# arpie_cv_tab.net
KiCad netlist of a schematic drawn in EAGLE
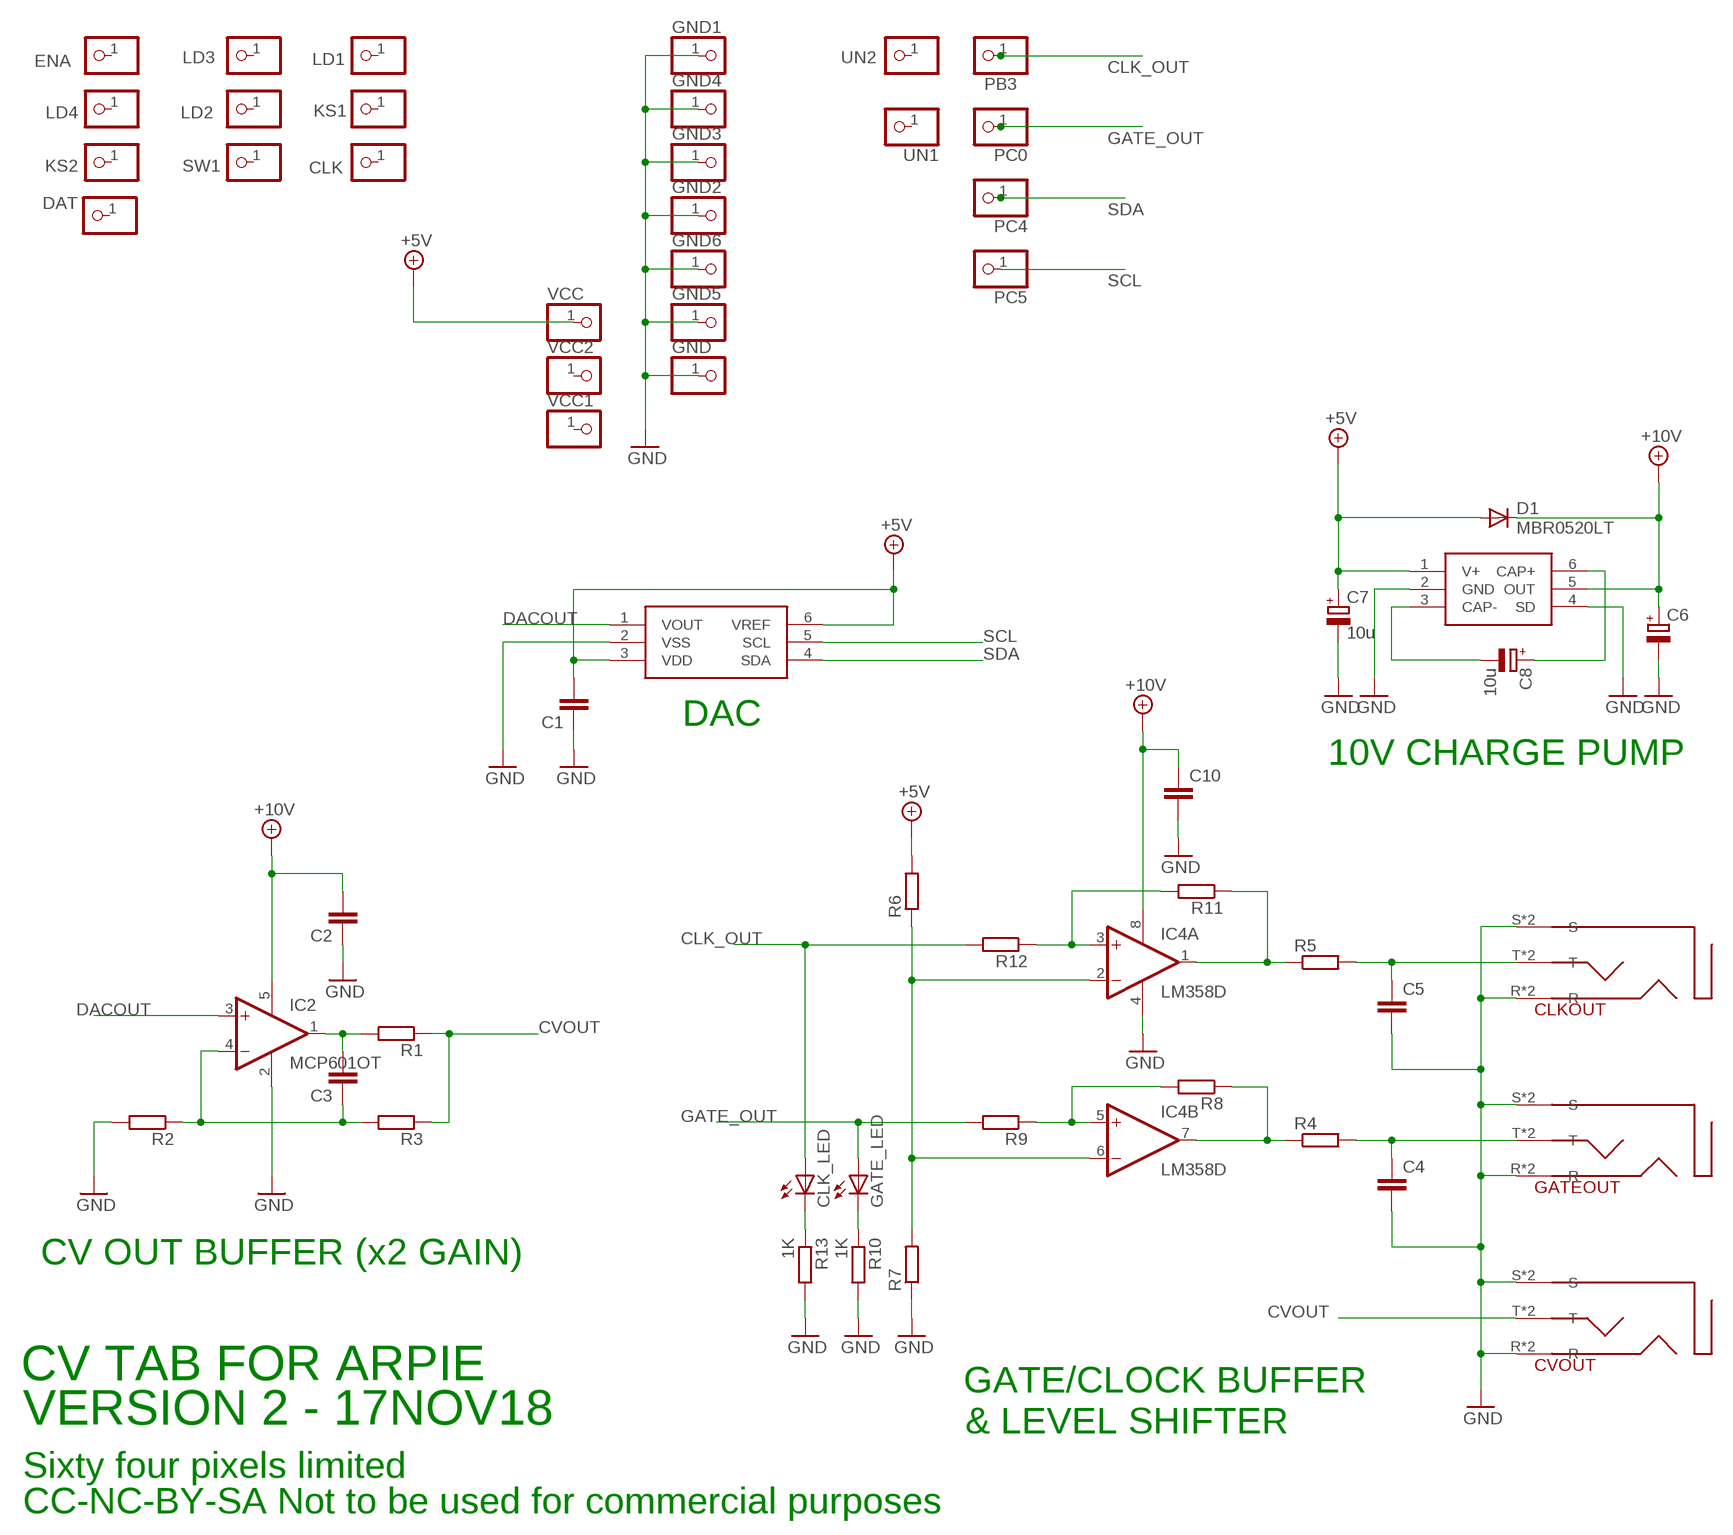
[diagram p0: schematic, sheet 1]

(export (version "E")
  (design (tool "Eeschema 10.0.6"))
  (components
    (comp (ref "C1")
      (value "C-EUC0805")
      (footprint "eagle-import:C0805")
      (libsource (lib "eagle-import") (part "C-EUC0805"))
    )
    (comp (ref "C2")
      (value "C-EUC0805")
      (footprint "eagle-import:C0805")
      (libsource (lib "eagle-import") (part "C-EUC0805"))
    )
    (comp (ref "C3")
      (value "C-EUC0805")
      (footprint "eagle-import:C0805")
      (libsource (lib "eagle-import") (part "C-EUC0805"))
    )
    (comp (ref "C4")
      (value "C-EUC0805")
      (footprint "eagle-import:C0805")
      (libsource (lib "eagle-import") (part "C-EUC0805"))
    )
    (comp (ref "C5")
      (value "C-EUC0805")
      (footprint "eagle-import:C0805")
      (libsource (lib "eagle-import") (part "C-EUC0805"))
    )
    (comp (ref "C6")
      (value "CPOL-EUSMCA")
      (footprint "eagle-import:SMC_A")
      (libsource (lib "eagle-import") (part "CPOL-EUSMCA"))
    )
    (comp (ref "C7")
      (value "10u")
      (footprint "eagle-import:SMC_A")
      (libsource (lib "eagle-import") (part "CPOL-EUSMCA"))
    )
    (comp (ref "C8")
      (value "10u")
      (footprint "eagle-import:SMC_A")
      (libsource (lib "eagle-import") (part "CPOL-EUSMCA"))
    )
    (comp (ref "C10")
      (value "C-EUC0805")
      (footprint "eagle-import:C0805")
      (libsource (lib "eagle-import") (part "C-EUC0805"))
    )
    (comp (ref "CLK")
      (value "PINHD-1X1")
      (footprint "eagle-import:1X01")
      (libsource (lib "eagle-import") (part "PINHD-1X1"))
    )
    (comp (ref "CLKOUT")
      (value "SMD35MMJACK")
      (footprint "eagle-import:SMD35MMJACK")
      (libsource (lib "eagle-import") (part "SMD35MMJACK"))
    )
    (comp (ref "CLK_LED")
      (value "LED3MM")
      (footprint "eagle-import:LED3MM")
      (libsource (lib "eagle-import") (part "LED3MM"))
    )
    (comp (ref "CVOUT")
      (value "SMD35MMJACK")
      (footprint "eagle-import:SMD35MMJACK")
      (libsource (lib "eagle-import") (part "SMD35MMJACK"))
    )
    (comp (ref "D1")
      (value "MBR0520LT")
      (footprint "eagle-import:SOD123")
      (libsource (lib "eagle-import") (part "MBR0520LT"))
    )
    (comp (ref "DAT")
      (value "PINHD-1X1")
      (footprint "eagle-import:1X01")
      (libsource (lib "eagle-import") (part "PINHD-1X1"))
    )
    (comp (ref "ENA")
      (value "PINHD-1X1")
      (footprint "eagle-import:1X01")
      (libsource (lib "eagle-import") (part "PINHD-1X1"))
    )
    (comp (ref "GATEOUT")
      (value "SMD35MMJACK")
      (footprint "eagle-import:SMD35MMJACK")
      (libsource (lib "eagle-import") (part "SMD35MMJACK"))
    )
    (comp (ref "GATE_LED")
      (value "LED3MM")
      (footprint "eagle-import:LED3MM")
      (libsource (lib "eagle-import") (part "LED3MM"))
    )
    (comp (ref "GND")
      (value "PINHD-1X1")
      (footprint "eagle-import:1X01")
      (libsource (lib "eagle-import") (part "PINHD-1X1"))
    )
    (comp (ref "GND1")
      (value "PINHD-1X1")
      (footprint "eagle-import:1X01")
      (libsource (lib "eagle-import") (part "PINHD-1X1"))
    )
    (comp (ref "GND2")
      (value "PINHD-1X1")
      (footprint "eagle-import:1X01")
      (libsource (lib "eagle-import") (part "PINHD-1X1"))
    )
    (comp (ref "GND3")
      (value "PINHD-1X1")
      (footprint "eagle-import:1X01")
      (libsource (lib "eagle-import") (part "PINHD-1X1"))
    )
    (comp (ref "GND4")
      (value "PINHD-1X1")
      (footprint "eagle-import:1X01")
      (libsource (lib "eagle-import") (part "PINHD-1X1"))
    )
    (comp (ref "GND5")
      (value "PINHD-1X1")
      (footprint "eagle-import:1X01")
      (libsource (lib "eagle-import") (part "PINHD-1X1"))
    )
    (comp (ref "GND6")
      (value "PINHD-1X1")
      (footprint "eagle-import:1X01")
      (libsource (lib "eagle-import") (part "PINHD-1X1"))
    )
    (comp (ref "IC1")
      (value "MCP4726")
      (footprint "eagle-import:SOT23-6")
      (libsource (lib "eagle-import") (part "MCP4726"))
    )
    (comp (ref "IC2")
      (value "MCP601OT")
      (footprint "eagle-import:SOT23-5")
      (libsource (lib "eagle-import") (part "MCP601OT"))
    )
    (comp (ref "IC3")
      (value "LM27675M5_CHARGEPUMP")
      (footprint "eagle-import:SOT23-6")
      (libsource (lib "eagle-import") (part "LM27675M5_CHARGEPUMP"))
    )
    (comp (ref "IC4")
      (value "LM358D")
      (footprint "eagle-import:SO08")
      (libsource (lib "eagle-import") (part "LM358D"))
    )
    (comp (ref "KS1")
      (value "PINHD-1X1")
      (footprint "eagle-import:1X01")
      (libsource (lib "eagle-import") (part "PINHD-1X1"))
    )
    (comp (ref "KS2")
      (value "PINHD-1X1")
      (footprint "eagle-import:1X01")
      (libsource (lib "eagle-import") (part "PINHD-1X1"))
    )
    (comp (ref "LD1")
      (value "PINHD-1X1")
      (footprint "eagle-import:1X01")
      (libsource (lib "eagle-import") (part "PINHD-1X1"))
    )
    (comp (ref "LD2")
      (value "PINHD-1X1")
      (footprint "eagle-import:1X01")
      (libsource (lib "eagle-import") (part "PINHD-1X1"))
    )
    (comp (ref "LD3")
      (value "PINHD-1X1")
      (footprint "eagle-import:1X01")
      (libsource (lib "eagle-import") (part "PINHD-1X1"))
    )
    (comp (ref "LD4")
      (value "PINHD-1X1")
      (footprint "eagle-import:1X01")
      (libsource (lib "eagle-import") (part "PINHD-1X1"))
    )
    (comp (ref "PB3")
      (value "PINHD-1X1")
      (footprint "eagle-import:1X01")
      (libsource (lib "eagle-import") (part "PINHD-1X1"))
    )
    (comp (ref "PC0")
      (value "PINHD-1X1")
      (footprint "eagle-import:1X01")
      (libsource (lib "eagle-import") (part "PINHD-1X1"))
    )
    (comp (ref "PC4")
      (value "PINHD-1X1")
      (footprint "eagle-import:1X01")
      (libsource (lib "eagle-import") (part "PINHD-1X1"))
    )
    (comp (ref "PC5")
      (value "PINHD-1X1")
      (footprint "eagle-import:1X01")
      (libsource (lib "eagle-import") (part "PINHD-1X1"))
    )
    (comp (ref "R1")
      (value "R-EU_R0805")
      (footprint "eagle-import:R0805")
      (libsource (lib "eagle-import") (part "R-EU_R0805"))
    )
    (comp (ref "R2")
      (value "R-EU_R0805")
      (footprint "eagle-import:R0805")
      (libsource (lib "eagle-import") (part "R-EU_R0805"))
    )
    (comp (ref "R3")
      (value "R-EU_R0805")
      (footprint "eagle-import:R0805")
      (libsource (lib "eagle-import") (part "R-EU_R0805"))
    )
    (comp (ref "R4")
      (value "R-EU_R0805")
      (footprint "eagle-import:R0805")
      (libsource (lib "eagle-import") (part "R-EU_R0805"))
    )
    (comp (ref "R5")
      (value "R-EU_R0805")
      (footprint "eagle-import:R0805")
      (libsource (lib "eagle-import") (part "R-EU_R0805"))
    )
    (comp (ref "R6")
      (value "R-EU_R0805")
      (footprint "eagle-import:R0805")
      (libsource (lib "eagle-import") (part "R-EU_R0805"))
    )
    (comp (ref "R7")
      (value "R-EU_R0805")
      (footprint "eagle-import:R0805")
      (libsource (lib "eagle-import") (part "R-EU_R0805"))
    )
    (comp (ref "R8")
      (value "R-EU_R0805")
      (footprint "eagle-import:R0805")
      (libsource (lib "eagle-import") (part "R-EU_R0805"))
    )
    (comp (ref "R9")
      (value "R-EU_R0805")
      (footprint "eagle-import:R0805")
      (libsource (lib "eagle-import") (part "R-EU_R0805"))
    )
    (comp (ref "R10")
      (value "1K")
      (footprint "eagle-import:R0805")
      (libsource (lib "eagle-import") (part "R-EU_R0805"))
    )
    (comp (ref "R11")
      (value "R-EU_R0805")
      (footprint "eagle-import:R0805")
      (libsource (lib "eagle-import") (part "R-EU_R0805"))
    )
    (comp (ref "R12")
      (value "R-EU_R0805")
      (footprint "eagle-import:R0805")
      (libsource (lib "eagle-import") (part "R-EU_R0805"))
    )
    (comp (ref "R13")
      (value "1K")
      (footprint "eagle-import:R0805")
      (libsource (lib "eagle-import") (part "R-EU_R0805"))
    )
    (comp (ref "SW1")
      (value "PINHD-1X1")
      (footprint "eagle-import:1X01")
      (libsource (lib "eagle-import") (part "PINHD-1X1"))
    )
    (comp (ref "UN1")
      (value "PINHD-1X1")
      (footprint "eagle-import:1X01")
      (libsource (lib "eagle-import") (part "PINHD-1X1"))
    )
    (comp (ref "UN2")
      (value "PINHD-1X1")
      (footprint "eagle-import:1X01")
      (libsource (lib "eagle-import") (part "PINHD-1X1"))
    )
    (comp (ref "VCC")
      (value "PINHD-1X1")
      (footprint "eagle-import:1X01")
      (libsource (lib "eagle-import") (part "PINHD-1X1"))
    )
    (comp (ref "VCC1")
      (value "PINHD-1X1")
      (footprint "eagle-import:1X01")
      (libsource (lib "eagle-import") (part "PINHD-1X1"))
    )
    (comp (ref "VCC2")
      (value "PINHD-1X1")
      (footprint "eagle-import:1X01")
      (libsource (lib "eagle-import") (part "PINHD-1X1"))
    )
  )
  (nets
    (net (code "1") (name "+5V") (class "Default")
      (node (ref "C1") (pin "2") (pinfunction "2_2") (pintype "passive"))
      (node (ref "C7") (pin "+") (pinfunction "+_+") (pintype "passive"))
      (node (ref "D1") (pin "A") (pinfunction "A_A") (pintype "passive"))
      (node (ref "IC1") (pin "3") (pinfunction "VDD_3") (pintype "power_in"))
      (node (ref "IC1") (pin "6") (pinfunction "VREF_6") (pintype "input"))
      (node (ref "IC3") (pin "1") (pinfunction "V+_1") (pintype "bidirectional"))
      (node (ref "R6") (pin "2") (pinfunction "2_2") (pintype "passive"))
      (node (ref "VCC") (pin "1") (pinfunction "1_1") (pintype "passive"))
    )
    (net (code "2") (name "+10V") (class "Default")
      (node (ref "C10") (pin "1") (pinfunction "1_1") (pintype "passive"))
      (node (ref "C2") (pin "2") (pinfunction "2_2") (pintype "passive"))
      (node (ref "C6") (pin "+") (pinfunction "+_+") (pintype "passive"))
      (node (ref "D1") (pin "C") (pinfunction "C_C") (pintype "passive"))
      (node (ref "IC2") (pin "5") (pinfunction "V+_5") (pintype "power_in"))
      (node (ref "IC3") (pin "5") (pinfunction "OUT_5") (pintype "bidirectional"))
      (node (ref "IC4") (pin "8") (pinfunction "V+_8") (pintype "power_in"))
    )
    (net (code "3") (name "/CLK_OUT") (class "Default")
      (node (ref "CLK_LED") (pin "A") (pinfunction "A_A") (pintype "passive"))
      (node (ref "PB3") (pin "1") (pinfunction "1_1") (pintype "passive"))
      (node (ref "R12") (pin "2") (pinfunction "2_2") (pintype "passive"))
    )
    (net (code "4") (name "/CVOUT") (class "Default")
      (node (ref "CVOUT") (pin "T") (pinfunction "T_T") (pintype "bidirectional"))
      (node (ref "CVOUT") (pin "T@") (pinfunction "T_T@") (pintype "bidirectional"))
      (node (ref "R1") (pin "1") (pinfunction "1_1") (pintype "passive"))
      (node (ref "R3") (pin "1") (pinfunction "1_1") (pintype "passive"))
    )
    (net (code "5") (name "/DACOUT") (class "Default")
      (node (ref "IC1") (pin "1") (pinfunction "VOUT_1") (pintype "output"))
      (node (ref "IC2") (pin "3") (pinfunction "+IN_3") (pintype "input"))
    )
    (net (code "6") (name "/GATE_OUT") (class "Default")
      (node (ref "GATE_LED") (pin "A") (pinfunction "A_A") (pintype "passive"))
      (node (ref "PC0") (pin "1") (pinfunction "1_1") (pintype "passive"))
      (node (ref "R9") (pin "2") (pinfunction "2_2") (pintype "passive"))
    )
    (net (code "7") (name "/SCL") (class "Default")
      (node (ref "IC1") (pin "5") (pinfunction "SCL_5") (pintype "bidirectional"))
      (node (ref "PC5") (pin "1") (pinfunction "1_1") (pintype "passive"))
    )
    (net (code "8") (name "/SDA") (class "Default")
      (node (ref "IC1") (pin "4") (pinfunction "SDA_4") (pintype "bidirectional"))
      (node (ref "PC4") (pin "1") (pinfunction "1_1") (pintype "passive"))
    )
    (net (code "9") (name "GND") (class "Default")
      (node (ref "C1") (pin "1") (pinfunction "1_1") (pintype "passive"))
      (node (ref "C10") (pin "2") (pinfunction "2_2") (pintype "passive"))
      (node (ref "C2") (pin "1") (pinfunction "1_1") (pintype "passive"))
      (node (ref "C4") (pin "2") (pinfunction "2_2") (pintype "passive"))
      (node (ref "C5") (pin "2") (pinfunction "2_2") (pintype "passive"))
      (node (ref "C6") (pin "-") (pinfunction "-_-") (pintype "passive"))
      (node (ref "C7") (pin "-") (pinfunction "-_-") (pintype "passive"))
      (node (ref "CLKOUT") (pin "R") (pinfunction "R_R") (pintype "bidirectional"))
      (node (ref "CLKOUT") (pin "R@") (pinfunction "R_R@") (pintype "bidirectional"))
      (node (ref "CLKOUT") (pin "S") (pinfunction "S_S") (pintype "bidirectional"))
      (node (ref "CLKOUT") (pin "S@") (pinfunction "S_S@") (pintype "bidirectional"))
      (node (ref "CVOUT") (pin "R") (pinfunction "R_R") (pintype "bidirectional"))
      (node (ref "CVOUT") (pin "R@") (pinfunction "R_R@") (pintype "bidirectional"))
      (node (ref "CVOUT") (pin "S") (pinfunction "S_S") (pintype "bidirectional"))
      (node (ref "CVOUT") (pin "S@") (pinfunction "S_S@") (pintype "bidirectional"))
      (node (ref "GATEOUT") (pin "R") (pinfunction "R_R") (pintype "bidirectional"))
      (node (ref "GATEOUT") (pin "R@") (pinfunction "R_R@") (pintype "bidirectional"))
      (node (ref "GATEOUT") (pin "S") (pinfunction "S_S") (pintype "bidirectional"))
      (node (ref "GATEOUT") (pin "S@") (pinfunction "S_S@") (pintype "bidirectional"))
      (node (ref "GND") (pin "1") (pinfunction "1_1") (pintype "passive"))
      (node (ref "GND1") (pin "1") (pinfunction "1_1") (pintype "passive"))
      (node (ref "GND2") (pin "1") (pinfunction "1_1") (pintype "passive"))
      (node (ref "GND3") (pin "1") (pinfunction "1_1") (pintype "passive"))
      (node (ref "GND4") (pin "1") (pinfunction "1_1") (pintype "passive"))
      (node (ref "GND5") (pin "1") (pinfunction "1_1") (pintype "passive"))
      (node (ref "GND6") (pin "1") (pinfunction "1_1") (pintype "passive"))
      (node (ref "IC1") (pin "2") (pinfunction "VSS_2") (pintype "power_in"))
      (node (ref "IC2") (pin "2") (pinfunction "V-_2") (pintype "power_in"))
      (node (ref "IC3") (pin "2") (pinfunction "GND_2") (pintype "bidirectional"))
      (node (ref "IC3") (pin "4") (pinfunction "SD_4") (pintype "bidirectional"))
      (node (ref "IC4") (pin "4") (pinfunction "V-_4") (pintype "power_in"))
      (node (ref "R10") (pin "2") (pinfunction "2_2") (pintype "passive"))
      (node (ref "R13") (pin "2") (pinfunction "2_2") (pintype "passive"))
      (node (ref "R2") (pin "2") (pinfunction "2_2") (pintype "passive"))
      (node (ref "R7") (pin "1") (pinfunction "1_1") (pintype "passive"))
    )
    (net (code "10") (name "Net-(C4-Pad1)") (class "Default")
      (node (ref "C4") (pin "1") (pinfunction "1_1") (pintype "passive"))
      (node (ref "GATEOUT") (pin "T") (pinfunction "T_T") (pintype "bidirectional"))
      (node (ref "GATEOUT") (pin "T@") (pinfunction "T_T@") (pintype "bidirectional"))
      (node (ref "R4") (pin "2") (pinfunction "2_2") (pintype "passive"))
    )
    (net (code "11") (name "Net-(C5-Pad1)") (class "Default")
      (node (ref "C5") (pin "1") (pinfunction "1_1") (pintype "passive"))
      (node (ref "CLKOUT") (pin "T") (pinfunction "T_T") (pintype "bidirectional"))
      (node (ref "CLKOUT") (pin "T@") (pinfunction "T_T@") (pintype "bidirectional"))
      (node (ref "R5") (pin "2") (pinfunction "2_2") (pintype "passive"))
    )
    (net (code "12") (name "Net-(CLK_LED-C)") (class "Default")
      (node (ref "CLK_LED") (pin "K") (pinfunction "C_K") (pintype "passive"))
      (node (ref "R13") (pin "1") (pinfunction "1_1") (pintype "passive"))
    )
    (net (code "13") (name "Net-(GATE_LED-C)") (class "Default")
      (node (ref "GATE_LED") (pin "K") (pinfunction "C_K") (pintype "passive"))
      (node (ref "R10") (pin "1") (pinfunction "1_1") (pintype "passive"))
    )
    (net (code "14") (name "Net-(IC2--IN)") (class "Default")
      (node (ref "C3") (pin "1") (pinfunction "1_1") (pintype "passive"))
      (node (ref "IC2") (pin "4") (pinfunction "-IN_4") (pintype "input"))
      (node (ref "R2") (pin "1") (pinfunction "1_1") (pintype "passive"))
      (node (ref "R3") (pin "2") (pinfunction "2_2") (pintype "passive"))
    )
    (net (code "15") (name "Net-(IC2-OUT)") (class "Default")
      (node (ref "C3") (pin "2") (pinfunction "2_2") (pintype "passive"))
      (node (ref "IC2") (pin "1") (pinfunction "OUT_1") (pintype "output"))
      (node (ref "R1") (pin "2") (pinfunction "2_2") (pintype "passive"))
    )
    (net (code "16") (name "Net-(IC3-CAP+)") (class "Default")
      (node (ref "C8") (pin "+") (pinfunction "+_+") (pintype "passive"))
      (node (ref "IC3") (pin "6") (pinfunction "CAP+_6") (pintype "bidirectional"))
    )
    (net (code "17") (name "Net-(IC3-CAP-)") (class "Default")
      (node (ref "C8") (pin "-") (pinfunction "-_-") (pintype "passive"))
      (node (ref "IC3") (pin "3") (pinfunction "CAP-_3") (pintype "bidirectional"))
    )
    (net (code "18") (name "Net-(IC4A-+IN)") (class "Default")
      (node (ref "IC4") (pin "3") (pinfunction "+IN_3") (pintype "input"))
      (node (ref "R11") (pin "2") (pinfunction "2_2") (pintype "passive"))
      (node (ref "R12") (pin "1") (pinfunction "1_1") (pintype "passive"))
    )
    (net (code "19") (name "Net-(IC4A--IN)") (class "Default")
      (node (ref "IC4") (pin "2") (pinfunction "-IN_2") (pintype "input"))
      (node (ref "IC4") (pin "6") (pinfunction "-IN_6") (pintype "input"))
      (node (ref "R6") (pin "1") (pinfunction "1_1") (pintype "passive"))
      (node (ref "R7") (pin "2") (pinfunction "2_2") (pintype "passive"))
    )
    (net (code "20") (name "Net-(IC4A-OUT)") (class "Default")
      (node (ref "IC4") (pin "1") (pinfunction "OUT_1") (pintype "output"))
      (node (ref "R11") (pin "1") (pinfunction "1_1") (pintype "passive"))
      (node (ref "R5") (pin "1") (pinfunction "1_1") (pintype "passive"))
    )
    (net (code "21") (name "Net-(IC4B-+IN)") (class "Default")
      (node (ref "IC4") (pin "5") (pinfunction "+IN_5") (pintype "input"))
      (node (ref "R8") (pin "2") (pinfunction "2_2") (pintype "passive"))
      (node (ref "R9") (pin "1") (pinfunction "1_1") (pintype "passive"))
    )
    (net (code "22") (name "Net-(IC4B-OUT)") (class "Default")
      (node (ref "IC4") (pin "7") (pinfunction "OUT_7") (pintype "output"))
      (node (ref "R4") (pin "1") (pinfunction "1_1") (pintype "passive"))
      (node (ref "R8") (pin "1") (pinfunction "1_1") (pintype "passive"))
    )
    (net (code "23") (name "unconnected-(CLK-Pad1)") (class "Default")
      (node (ref "CLK") (pin "1") (pinfunction "1_1") (pintype "passive"))
    )
    (net (code "24") (name "unconnected-(DAT-Pad1)") (class "Default")
      (node (ref "DAT") (pin "1") (pinfunction "1_1") (pintype "passive"))
    )
    (net (code "25") (name "unconnected-(ENA-Pad1)") (class "Default")
      (node (ref "ENA") (pin "1") (pinfunction "1_1") (pintype "passive"))
    )
    (net (code "26") (name "unconnected-(KS1-Pad1)") (class "Default")
      (node (ref "KS1") (pin "1") (pinfunction "1_1") (pintype "passive"))
    )
    (net (code "27") (name "unconnected-(KS2-Pad1)") (class "Default")
      (node (ref "KS2") (pin "1") (pinfunction "1_1") (pintype "passive"))
    )
    (net (code "28") (name "unconnected-(LD1-Pad1)") (class "Default")
      (node (ref "LD1") (pin "1") (pinfunction "1_1") (pintype "passive"))
    )
    (net (code "29") (name "unconnected-(LD2-Pad1)") (class "Default")
      (node (ref "LD2") (pin "1") (pinfunction "1_1") (pintype "passive"))
    )
    (net (code "30") (name "unconnected-(LD3-Pad1)") (class "Default")
      (node (ref "LD3") (pin "1") (pinfunction "1_1") (pintype "passive"))
    )
    (net (code "31") (name "unconnected-(LD4-Pad1)") (class "Default")
      (node (ref "LD4") (pin "1") (pinfunction "1_1") (pintype "passive"))
    )
    (net (code "32") (name "unconnected-(SW1-Pad1)") (class "Default")
      (node (ref "SW1") (pin "1") (pinfunction "1_1") (pintype "passive"))
    )
    (net (code "33") (name "unconnected-(UN1-Pad1)") (class "Default")
      (node (ref "UN1") (pin "1") (pinfunction "1_1") (pintype "passive"))
    )
    (net (code "34") (name "unconnected-(UN2-Pad1)") (class "Default")
      (node (ref "UN2") (pin "1") (pinfunction "1_1") (pintype "passive"))
    )
    (net (code "35") (name "unconnected-(VCC1-Pad1)") (class "Default")
      (node (ref "VCC1") (pin "1") (pinfunction "1_1") (pintype "passive"))
    )
    (net (code "36") (name "unconnected-(VCC2-Pad1)") (class "Default")
      (node (ref "VCC2") (pin "1") (pinfunction "1_1") (pintype "passive"))
    )
  )
)
